# P1.net
KiCad netlist of a schematic drawn in EAGLE
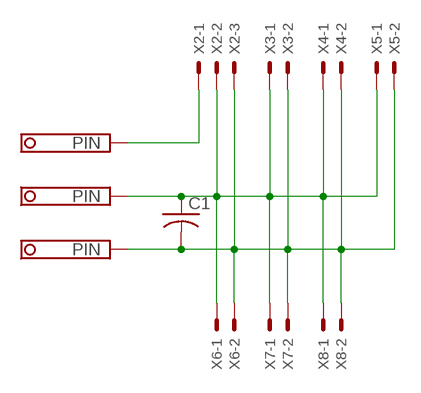
[diagram p0: schematic, sheet 1]

(export (version "E")
  (design (tool "Eeschema 10.0.6"))
  (components
    (comp (ref "C1")
      (value "C-US050-024X044")
      (footprint "eagle-import:C050-024X044")
      (libsource (lib "eagle-import") (part "C-US050-024X044"))
    )
    (comp (ref "X1")
      (value "TERMINAL-BLOCK-3.5MM-3-PIN-ROUND-PAD")
      (footprint "eagle-import:TERMINAL-BLOCK-3-PIN-3.5MM-ROUND-PAD")
      (libsource (lib "eagle-import") (part "TERMINAL-BLOCK-3.5MM-3-PIN-ROUND-PAD"))
    )
    (comp (ref "X2")
      (value "JST-XH-03-PIN-ROUND-PAD")
      (footprint "eagle-import:JST-XH-03-PACKAGE-ROUND-PAD")
      (libsource (lib "eagle-import") (part "JST-XH-03-PIN-ROUND-PAD"))
    )
    (comp (ref "X3")
      (value "JST-XH-02-PIN-ROUND-PAD")
      (footprint "eagle-import:JST-XH-02-PACKAGE-ROUND-PAD")
      (libsource (lib "eagle-import") (part "JST-XH-02-PIN-ROUND-PAD"))
    )
    (comp (ref "X4")
      (value "JST-XH-02-PIN-ROUND-PAD")
      (footprint "eagle-import:JST-XH-02-PACKAGE-ROUND-PAD")
      (libsource (lib "eagle-import") (part "JST-XH-02-PIN-ROUND-PAD"))
    )
    (comp (ref "X5")
      (value "JST-XH-02-PIN-ROUND-PAD")
      (footprint "eagle-import:JST-XH-02-PACKAGE-ROUND-PAD")
      (libsource (lib "eagle-import") (part "JST-XH-02-PIN-ROUND-PAD"))
    )
    (comp (ref "X6")
      (value "JST-XH-02-PIN-ROUND-PAD")
      (footprint "eagle-import:JST-XH-02-PACKAGE-ROUND-PAD")
      (libsource (lib "eagle-import") (part "JST-XH-02-PIN-ROUND-PAD"))
    )
    (comp (ref "X7")
      (value "JST-XH-02-PIN-ROUND-PAD")
      (footprint "eagle-import:JST-XH-02-PACKAGE-ROUND-PAD")
      (libsource (lib "eagle-import") (part "JST-XH-02-PIN-ROUND-PAD"))
    )
    (comp (ref "X8")
      (value "JST-XH-02-PIN-ROUND-PAD")
      (footprint "eagle-import:JST-XH-02-PACKAGE-ROUND-PAD")
      (libsource (lib "eagle-import") (part "JST-XH-02-PIN-ROUND-PAD"))
    )
  )
  (nets
    (net (code "1") (name "Net-(X1A-VCC)") (class "Default")
      (node (ref "X1") (pin "1") (pinfunction "VCC_1") (pintype "passive"))
      (node (ref "X2") (pin "1") (pinfunction "S_1") (pintype "passive"))
    )
    (net (code "2") (name "Net-(X1B-VCC)") (class "Default")
      (node (ref "C1") (pin "1") (pinfunction "1_1") (pintype "passive"))
      (node (ref "X1") (pin "2") (pinfunction "VCC_2") (pintype "passive"))
      (node (ref "X2") (pin "2") (pinfunction "S_2") (pintype "passive"))
      (node (ref "X3") (pin "1") (pinfunction "S_1") (pintype "passive"))
      (node (ref "X4") (pin "1") (pinfunction "S_1") (pintype "passive"))
      (node (ref "X5") (pin "1") (pinfunction "S_1") (pintype "passive"))
      (node (ref "X6") (pin "1") (pinfunction "S_1") (pintype "passive"))
      (node (ref "X7") (pin "1") (pinfunction "S_1") (pintype "passive"))
      (node (ref "X8") (pin "1") (pinfunction "S_1") (pintype "passive"))
    )
    (net (code "3") (name "Net-(X1C-VCC)") (class "Default")
      (node (ref "C1") (pin "2") (pinfunction "2_2") (pintype "passive"))
      (node (ref "X1") (pin "3") (pinfunction "VCC_3") (pintype "passive"))
      (node (ref "X2") (pin "3") (pinfunction "S_3") (pintype "passive"))
      (node (ref "X3") (pin "2") (pinfunction "S_2") (pintype "passive"))
      (node (ref "X4") (pin "2") (pinfunction "S_2") (pintype "passive"))
      (node (ref "X5") (pin "2") (pinfunction "S_2") (pintype "passive"))
      (node (ref "X6") (pin "2") (pinfunction "S_2") (pintype "passive"))
      (node (ref "X7") (pin "2") (pinfunction "S_2") (pintype "passive"))
      (node (ref "X8") (pin "2") (pinfunction "S_2") (pintype "passive"))
    )
  )
)
